# ProProject_AT32F403A__2024-07-07.net
KiCad netlist of a schematic drawn in EasyEDA Pro
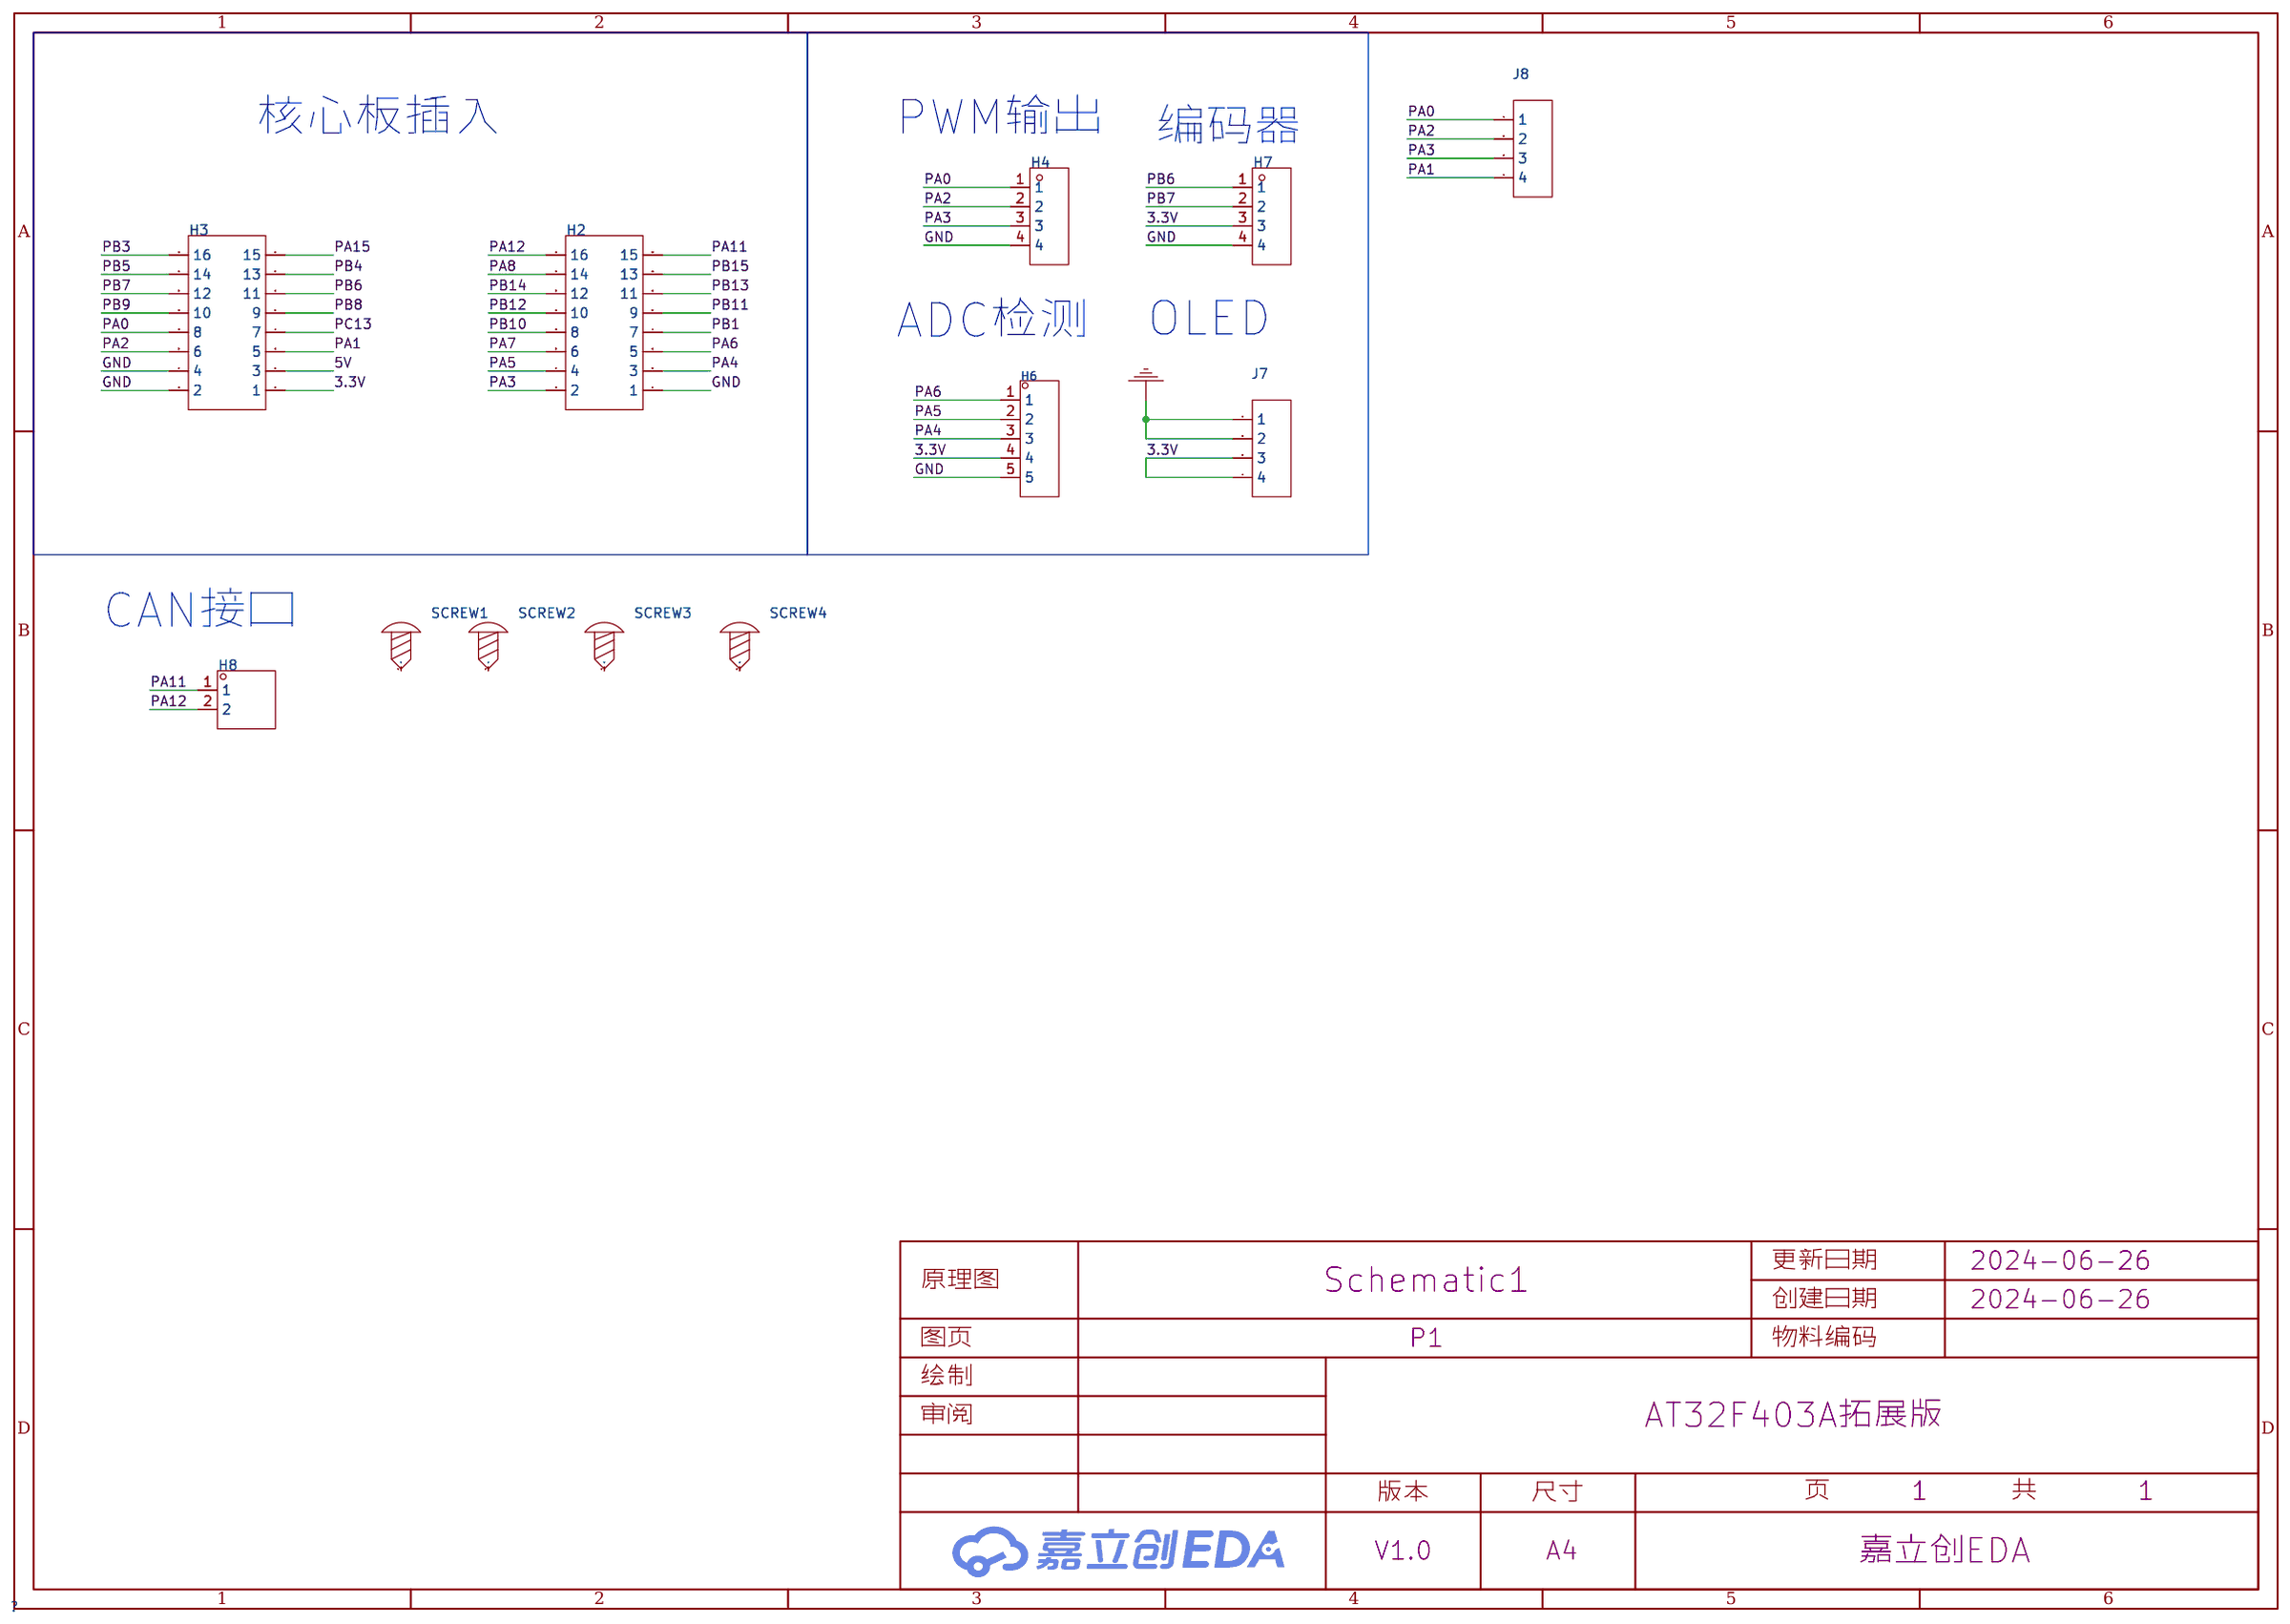
[diagram p0: schematic sheet]

(export (version "E")
  (design (tool "Eeschema 10.0.6"))
  (components
    (comp (ref "H2")
      (value "~")
      (footprint "easyedapro:HDR-TH_16P-P2.54-V-M-R2-C8-S2.54")
      (libsource (lib "easyedapro") (part "HDR-M-2.54_2x8"))
    )
    (comp (ref "H3")
      (value "~")
      (footprint "easyedapro:HDR-TH_16P-P2.54-V-M-R2-C8-S2.54")
      (libsource (lib "easyedapro") (part "HDR-M-2.54_2x8"))
    )
    (comp (ref "H4")
      (value "~")
      (footprint "easyedapro:HDR-TH_4P-P2.54-V-M")
      (libsource (lib "easyedapro") (part "PZ254V-11-04P"))
    )
    (comp (ref "H6")
      (value "~")
      (footprint "easyedapro:HDR-TH_5P-P2.54-V-M")
      (libsource (lib "easyedapro") (part "MTP125-1105S1"))
    )
    (comp (ref "H7")
      (value "~")
      (footprint "easyedapro:HDR-TH_4P-P2.54-V-M")
      (libsource (lib "easyedapro") (part "PZ254V-11-04P"))
    )
    (comp (ref "H8")
      (value "~")
      (footprint "easyedapro:HDR-TH_2P-P2.54-V-M-1")
      (libsource (lib "easyedapro") (part "210S-1*2P L=11.6MMGold-plated black"))
    )
    (comp (ref "J7")
      (value "HDR-M-2.54_1x4")
      (footprint "easyedapro:footprint_c5e7")
      (libsource (lib "easyedapro") (part "HDR-M-2.54_1x4"))
    )
    (comp (ref "J8")
      (value "HDR-M-2.54_1x4")
      (footprint "easyedapro:footprint_c5e7")
      (libsource (lib "easyedapro") (part "HDR-M-2.54_1x4"))
    )
    (comp (ref "SCREW1")
      (value "~")
      (footprint "easyedapro:M2螺丝")
      (libsource (lib "easyedapro") (part "螺丝孔"))
    )
    (comp (ref "SCREW2")
      (value "~")
      (footprint "easyedapro:M2螺丝")
      (libsource (lib "easyedapro") (part "螺丝孔"))
    )
    (comp (ref "SCREW3")
      (value "~")
      (footprint "easyedapro:M2螺丝")
      (libsource (lib "easyedapro") (part "螺丝孔"))
    )
    (comp (ref "SCREW4")
      (value "~")
      (footprint "easyedapro:M2螺丝")
      (libsource (lib "easyedapro") (part "螺丝孔"))
    )
  )
  (nets
    (net (code "1") (name "/3.3V") (class "Default")
      (node (ref "H3") (pin "1") (pinfunction "1_1") (pintype "input"))
      (node (ref "H6") (pin "4") (pinfunction "4_4") (pintype "input"))
      (node (ref "H7") (pin "3") (pinfunction "3_3") (pintype "unspecified"))
      (node (ref "J7") (pin "3") (pinfunction "3_3") (pintype "unspecified"))
      (node (ref "J7") (pin "4") (pinfunction "4_4") (pintype "unspecified"))
    )
    (net (code "2") (name "/5V") (class "Default")
      (node (ref "H3") (pin "3") (pinfunction "3_3") (pintype "input"))
    )
    (net (code "3") (name "/PA0") (class "Default")
      (node (ref "H3") (pin "8") (pinfunction "8_8") (pintype "input"))
      (node (ref "H4") (pin "1") (pinfunction "1_1") (pintype "unspecified"))
      (node (ref "J8") (pin "1") (pinfunction "1_1") (pintype "unspecified"))
    )
    (net (code "4") (name "/PA1") (class "Default")
      (node (ref "H3") (pin "5") (pinfunction "5_5") (pintype "input"))
      (node (ref "J8") (pin "4") (pinfunction "4_4") (pintype "unspecified"))
    )
    (net (code "5") (name "/PA2") (class "Default")
      (node (ref "H3") (pin "6") (pinfunction "6_6") (pintype "input"))
      (node (ref "H4") (pin "2") (pinfunction "2_2") (pintype "unspecified"))
      (node (ref "J8") (pin "2") (pinfunction "2_2") (pintype "unspecified"))
    )
    (net (code "6") (name "/PA3") (class "Default")
      (node (ref "H2") (pin "2") (pinfunction "2_2") (pintype "input"))
      (node (ref "H4") (pin "3") (pinfunction "3_3") (pintype "unspecified"))
      (node (ref "J8") (pin "3") (pinfunction "3_3") (pintype "unspecified"))
    )
    (net (code "7") (name "/PA4") (class "Default")
      (node (ref "H2") (pin "3") (pinfunction "3_3") (pintype "input"))
      (node (ref "H6") (pin "3") (pinfunction "3_3") (pintype "input"))
    )
    (net (code "8") (name "/PA5") (class "Default")
      (node (ref "H2") (pin "4") (pinfunction "4_4") (pintype "input"))
      (node (ref "H6") (pin "2") (pinfunction "2_2") (pintype "input"))
    )
    (net (code "9") (name "/PA6") (class "Default")
      (node (ref "H2") (pin "5") (pinfunction "5_5") (pintype "input"))
      (node (ref "H6") (pin "1") (pinfunction "1_1") (pintype "input"))
    )
    (net (code "10") (name "/PA7") (class "Default")
      (node (ref "H2") (pin "6") (pinfunction "6_6") (pintype "input"))
    )
    (net (code "11") (name "/PA8") (class "Default")
      (node (ref "H2") (pin "14") (pinfunction "14_14") (pintype "input"))
    )
    (net (code "12") (name "/PA11") (class "Default")
      (node (ref "H2") (pin "15") (pinfunction "15_15") (pintype "input"))
      (node (ref "H8") (pin "1") (pinfunction "1_1") (pintype "unspecified"))
    )
    (net (code "13") (name "/PA12") (class "Default")
      (node (ref "H2") (pin "16") (pinfunction "16_16") (pintype "input"))
      (node (ref "H8") (pin "2") (pinfunction "2_2") (pintype "unspecified"))
    )
    (net (code "14") (name "/PA15") (class "Default")
      (node (ref "H3") (pin "15") (pinfunction "15_15") (pintype "input"))
    )
    (net (code "15") (name "/PB1") (class "Default")
      (node (ref "H2") (pin "7") (pinfunction "7_7") (pintype "input"))
    )
    (net (code "16") (name "/PB3") (class "Default")
      (node (ref "H3") (pin "16") (pinfunction "16_16") (pintype "input"))
    )
    (net (code "17") (name "/PB4") (class "Default")
      (node (ref "H3") (pin "13") (pinfunction "13_13") (pintype "input"))
    )
    (net (code "18") (name "/PB5") (class "Default")
      (node (ref "H3") (pin "14") (pinfunction "14_14") (pintype "input"))
    )
    (net (code "19") (name "/PB6") (class "Default")
      (node (ref "H3") (pin "11") (pinfunction "11_11") (pintype "input"))
      (node (ref "H7") (pin "1") (pinfunction "1_1") (pintype "unspecified"))
    )
    (net (code "20") (name "/PB7") (class "Default")
      (node (ref "H3") (pin "12") (pinfunction "12_12") (pintype "input"))
      (node (ref "H7") (pin "2") (pinfunction "2_2") (pintype "unspecified"))
    )
    (net (code "21") (name "/PB8") (class "Default")
      (node (ref "H3") (pin "9") (pinfunction "9_9") (pintype "input"))
    )
    (net (code "22") (name "/PB9") (class "Default")
      (node (ref "H3") (pin "10") (pinfunction "10_10") (pintype "input"))
    )
    (net (code "23") (name "/PB10") (class "Default")
      (node (ref "H2") (pin "8") (pinfunction "8_8") (pintype "input"))
    )
    (net (code "24") (name "/PB11") (class "Default")
      (node (ref "H2") (pin "9") (pinfunction "9_9") (pintype "input"))
    )
    (net (code "25") (name "/PB12") (class "Default")
      (node (ref "H2") (pin "10") (pinfunction "10_10") (pintype "input"))
    )
    (net (code "26") (name "/PB13") (class "Default")
      (node (ref "H2") (pin "11") (pinfunction "11_11") (pintype "input"))
    )
    (net (code "27") (name "/PB14") (class "Default")
      (node (ref "H2") (pin "12") (pinfunction "12_12") (pintype "input"))
    )
    (net (code "28") (name "/PB15") (class "Default")
      (node (ref "H2") (pin "13") (pinfunction "13_13") (pintype "input"))
    )
    (net (code "29") (name "/PC13") (class "Default")
      (node (ref "H3") (pin "7") (pinfunction "7_7") (pintype "input"))
    )
    (net (code "30") (name "GND") (class "Default")
      (node (ref "H2") (pin "1") (pinfunction "1_1") (pintype "input"))
      (node (ref "H3") (pin "2") (pinfunction "2_2") (pintype "input"))
      (node (ref "H3") (pin "4") (pinfunction "4_4") (pintype "input"))
      (node (ref "H4") (pin "4") (pinfunction "4_4") (pintype "unspecified"))
      (node (ref "H6") (pin "5") (pinfunction "5_5") (pintype "input"))
      (node (ref "H7") (pin "4") (pinfunction "4_4") (pintype "unspecified"))
      (node (ref "J7") (pin "1") (pinfunction "1_1") (pintype "unspecified"))
      (node (ref "J7") (pin "2") (pinfunction "2_2") (pintype "unspecified"))
    )
    (net (code "31") (name "unconnected-(SCREW1-Pad1)") (class "Default")
      (node (ref "SCREW1") (pin "1") (pinfunction "1_1") (pintype "input"))
    )
    (net (code "32") (name "unconnected-(SCREW2-Pad1)") (class "Default")
      (node (ref "SCREW2") (pin "1") (pinfunction "1_1") (pintype "input"))
    )
    (net (code "33") (name "unconnected-(SCREW3-Pad1)") (class "Default")
      (node (ref "SCREW3") (pin "1") (pinfunction "1_1") (pintype "input"))
    )
    (net (code "34") (name "unconnected-(SCREW4-Pad1)") (class "Default")
      (node (ref "SCREW4") (pin "1") (pinfunction "1_1") (pintype "input"))
    )
  )
)
